# PSU.net
KiCad netlist of a schematic drawn in EAGLE
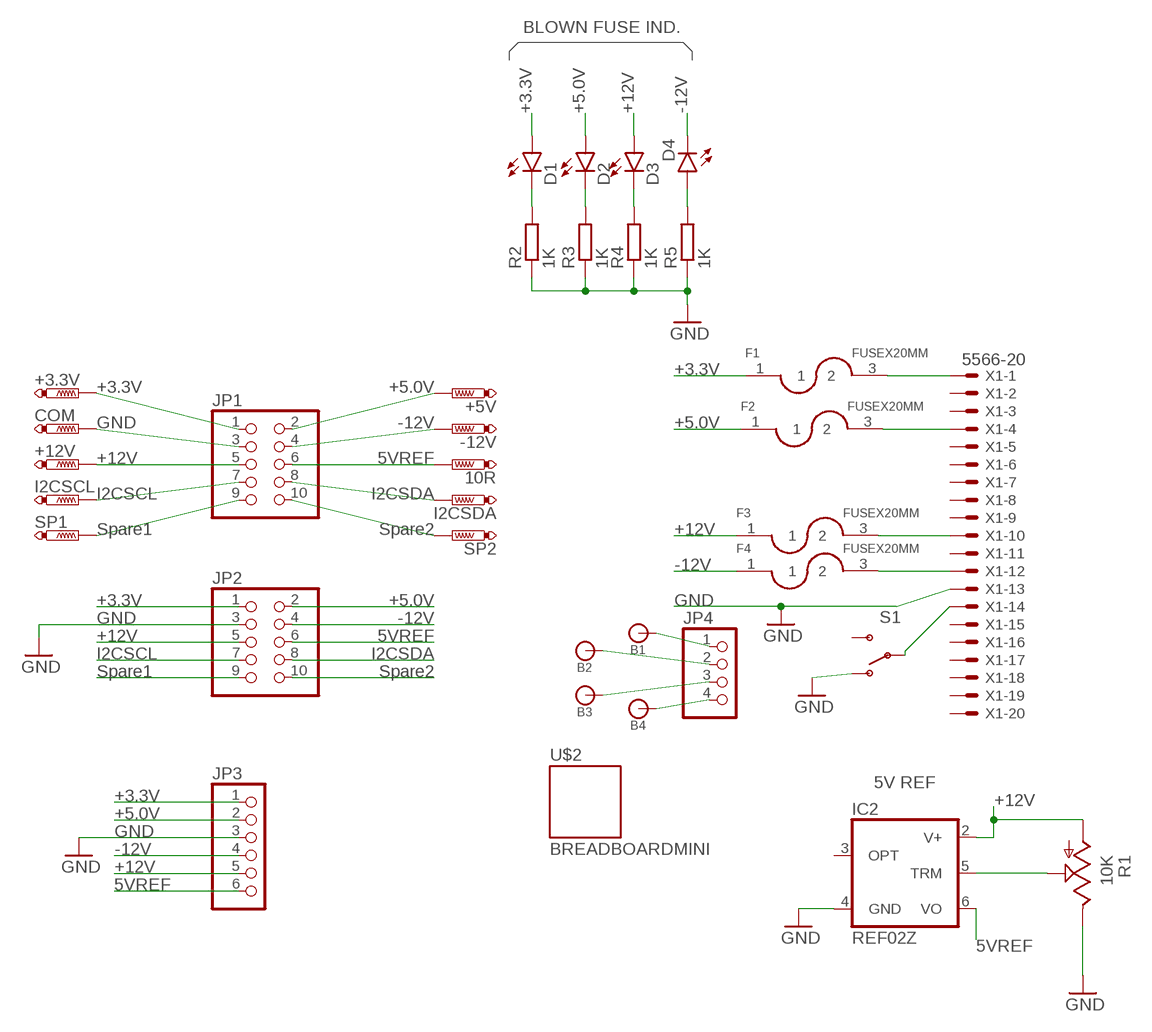
[diagram p0: schematic, sheet 1]

(export (version "E")
  (design (tool "Eeschema 10.0.6"))
  (components
    (comp (ref "+3.3V")
      (value "PTR1B1,27")
      (footprint "eagle-import:B1,27")
      (libsource (lib "eagle-import") (part "PTR1B1,27"))
    )
    (comp (ref "+5V")
      (value "PTR1B1,27")
      (footprint "eagle-import:B1,27")
      (libsource (lib "eagle-import") (part "PTR1B1,27"))
    )
    (comp (ref "+12V")
      (value "PTR1B1,27")
      (footprint "eagle-import:B1,27")
      (libsource (lib "eagle-import") (part "PTR1B1,27"))
    )
    (comp (ref "-12V")
      (value "PTR1B1,27")
      (footprint "eagle-import:B1,27")
      (libsource (lib "eagle-import") (part "PTR1B1,27"))
    )
    (comp (ref "10R")
      (value "PTR1B1,27")
      (footprint "eagle-import:B1,27")
      (libsource (lib "eagle-import") (part "PTR1B1,27"))
    )
    (comp (ref "B1")
      (value "BANANA_CONN")
      (footprint "eagle-import:BANANA_CONN")
      (libsource (lib "eagle-import") (part "BANANA_CONN"))
    )
    (comp (ref "B2")
      (value "BANANA_CONN")
      (footprint "eagle-import:BANANA_CONN")
      (libsource (lib "eagle-import") (part "BANANA_CONN"))
    )
    (comp (ref "B3")
      (value "BANANA_CONN")
      (footprint "eagle-import:BANANA_CONN")
      (libsource (lib "eagle-import") (part "BANANA_CONN"))
    )
    (comp (ref "B4")
      (value "BANANA_CONN")
      (footprint "eagle-import:BANANA_CONN")
      (libsource (lib "eagle-import") (part "BANANA_CONN"))
    )
    (comp (ref "COM")
      (value "PTR1B1,27")
      (footprint "eagle-import:B1,27")
      (libsource (lib "eagle-import") (part "PTR1B1,27"))
    )
    (comp (ref "D1")
      (value "LED5MM")
      (footprint "eagle-import:LED5MM")
      (libsource (lib "eagle-import") (part "LED5MM"))
    )
    (comp (ref "D2")
      (value "LED5MM")
      (footprint "eagle-import:LED5MM")
      (libsource (lib "eagle-import") (part "LED5MM"))
    )
    (comp (ref "D3")
      (value "LED5MM")
      (footprint "eagle-import:LED5MM")
      (libsource (lib "eagle-import") (part "LED5MM"))
    )
    (comp (ref "D4")
      (value "LED5MM")
      (footprint "eagle-import:LED5MM")
      (libsource (lib "eagle-import") (part "LED5MM"))
    )
    (comp (ref "F1")
      (value "FUSEX20MM")
      (footprint "eagle-import:FUSE_5MM")
      (libsource (lib "eagle-import") (part "FUSEX20MM"))
    )
    (comp (ref "F2")
      (value "FUSEX20MM")
      (footprint "eagle-import:FUSE_5MM")
      (libsource (lib "eagle-import") (part "FUSEX20MM"))
    )
    (comp (ref "F3")
      (value "FUSEX20MM")
      (footprint "eagle-import:FUSE_5MM")
      (libsource (lib "eagle-import") (part "FUSEX20MM"))
    )
    (comp (ref "F4")
      (value "FUSEX20MM")
      (footprint "eagle-import:FUSE_5MM")
      (libsource (lib "eagle-import") (part "FUSEX20MM"))
    )
    (comp (ref "I2CSCL")
      (value "PTR1B1,27")
      (footprint "eagle-import:B1,27")
      (libsource (lib "eagle-import") (part "PTR1B1,27"))
    )
    (comp (ref "I2CSDA")
      (value "PTR1B1,27")
      (footprint "eagle-import:B1,27")
      (libsource (lib "eagle-import") (part "PTR1B1,27"))
    )
    (comp (ref "IC2")
      (value "REF02Z")
      (footprint "eagle-import:DIL08")
      (libsource (lib "eagle-import") (part "REF02Z"))
    )
    (comp (ref "JP1")
      (value "PINHD-2X5/90")
      (footprint "eagle-import:2X05_90")
      (libsource (lib "eagle-import") (part "PINHD-2X5/90"))
    )
    (comp (ref "JP2")
      (value "PINHD-2X5/90")
      (footprint "eagle-import:2X05_90")
      (libsource (lib "eagle-import") (part "PINHD-2X5/90"))
    )
    (comp (ref "JP3")
      (value "PINHD-1X6")
      (footprint "eagle-import:1X06")
      (libsource (lib "eagle-import") (part "PINHD-1X6"))
    )
    (comp (ref "JP4")
      (value "PINHD-1X4")
      (footprint "eagle-import:1X04")
      (libsource (lib "eagle-import") (part "PINHD-1X4"))
    )
    (comp (ref "R1")
      (value "10K")
      (footprint "eagle-import:PT-10")
      (libsource (lib "eagle-import") (part "TRIM_US-PT-10"))
    )
    (comp (ref "R2")
      (value "1K")
      (footprint "eagle-import:RTH025W")
      (libsource (lib "eagle-import") (part "RESISTOR-PTH-0.4"))
    )
    (comp (ref "R3")
      (value "1K")
      (footprint "eagle-import:RTH025W")
      (libsource (lib "eagle-import") (part "RESISTOR-PTH-0.4"))
    )
    (comp (ref "R4")
      (value "1K")
      (footprint "eagle-import:RTH025W")
      (libsource (lib "eagle-import") (part "RESISTOR-PTH-0.4"))
    )
    (comp (ref "R5")
      (value "1K")
      (footprint "eagle-import:RTH025W")
      (libsource (lib "eagle-import") (part "RESISTOR-PTH-0.4"))
    )
    (comp (ref "S1")
      (value "SWITCH-SPDTPTH")
      (footprint "eagle-import:SWITCH-SPDT")
      (libsource (lib "eagle-import") (part "SWITCH-SPDTPTH"))
    )
    (comp (ref "SP1")
      (value "PTR1B1,27")
      (footprint "eagle-import:B1,27")
      (libsource (lib "eagle-import") (part "PTR1B1,27"))
    )
    (comp (ref "SP2")
      (value "PTR1B1,27")
      (footprint "eagle-import:B1,27")
      (libsource (lib "eagle-import") (part "PTR1B1,27"))
    )
    (comp (ref "U$2")
      (value "BREADBOARDMINI")
      (footprint "eagle-import:BREADBOARD-MINI")
      (libsource (lib "eagle-import") (part "BREADBOARDMINI"))
    )
    (comp (ref "X1")
      (value "5566-20")
      (footprint "eagle-import:5566-20")
      (libsource (lib "eagle-import") (part "5566-20"))
    )
  )
  (nets
    (net (code "1") (name "/+3.3V") (class "Default")
      (node (ref "+3.3V") (pin "TP") (pinfunction "TP_TP") (pintype "input"))
      (node (ref "D1") (pin "A") (pinfunction "A_A") (pintype "passive"))
      (node (ref "F1") (pin "1") (pinfunction "1_1") (pintype "bidirectional"))
      (node (ref "JP1") (pin "1") (pinfunction "1_1") (pintype "passive"))
      (node (ref "JP2") (pin "1") (pinfunction "1_1") (pintype "passive"))
      (node (ref "JP3") (pin "1") (pinfunction "1_1") (pintype "passive"))
    )
    (net (code "2") (name "/+5.0V") (class "Default")
      (node (ref "+5V") (pin "TP") (pinfunction "TP_TP") (pintype "input"))
      (node (ref "D2") (pin "A") (pinfunction "A_A") (pintype "passive"))
      (node (ref "F2") (pin "1") (pinfunction "1_1") (pintype "bidirectional"))
      (node (ref "JP1") (pin "2") (pinfunction "2_2") (pintype "passive"))
      (node (ref "JP2") (pin "2") (pinfunction "2_2") (pintype "passive"))
      (node (ref "JP3") (pin "2") (pinfunction "2_2") (pintype "passive"))
    )
    (net (code "3") (name "/+12V") (class "Default")
      (node (ref "+12V") (pin "TP") (pinfunction "TP_TP") (pintype "input"))
      (node (ref "D3") (pin "A") (pinfunction "A_A") (pintype "passive"))
      (node (ref "F3") (pin "1") (pinfunction "1_1") (pintype "bidirectional"))
      (node (ref "IC2") (pin "2") (pinfunction "V+_2") (pintype "power_in"))
      (node (ref "JP1") (pin "5") (pinfunction "5_5") (pintype "passive"))
      (node (ref "JP2") (pin "5") (pinfunction "5_5") (pintype "passive"))
      (node (ref "JP3") (pin "5") (pinfunction "5_5") (pintype "passive"))
      (node (ref "R1") (pin "A") (pinfunction "A_A") (pintype "passive"))
    )
    (net (code "4") (name "/-12V") (class "Default")
      (node (ref "-12V") (pin "TP") (pinfunction "TP_TP") (pintype "input"))
      (node (ref "D4") (pin "K") (pinfunction "C_K") (pintype "passive"))
      (node (ref "F4") (pin "1") (pinfunction "1_1") (pintype "bidirectional"))
      (node (ref "JP1") (pin "4") (pinfunction "4_4") (pintype "passive"))
      (node (ref "JP2") (pin "4") (pinfunction "4_4") (pintype "passive"))
      (node (ref "JP3") (pin "4") (pinfunction "4_4") (pintype "passive"))
    )
    (net (code "5") (name "/5VREF") (class "Default")
      (node (ref "10R") (pin "TP") (pinfunction "TP_TP") (pintype "input"))
      (node (ref "IC2") (pin "6") (pinfunction "VO_6") (pintype "output"))
      (node (ref "JP1") (pin "6") (pinfunction "6_6") (pintype "passive"))
      (node (ref "JP2") (pin "6") (pinfunction "6_6") (pintype "passive"))
      (node (ref "JP3") (pin "6") (pinfunction "6_6") (pintype "passive"))
    )
    (net (code "6") (name "/I2CSCL") (class "Default")
      (node (ref "I2CSCL") (pin "TP") (pinfunction "TP_TP") (pintype "input"))
      (node (ref "JP1") (pin "7") (pinfunction "7_7") (pintype "passive"))
      (node (ref "JP2") (pin "7") (pinfunction "7_7") (pintype "passive"))
    )
    (net (code "7") (name "/I2CSDA") (class "Default")
      (node (ref "I2CSDA") (pin "TP") (pinfunction "TP_TP") (pintype "input"))
      (node (ref "JP1") (pin "8") (pinfunction "8_8") (pintype "passive"))
      (node (ref "JP2") (pin "8") (pinfunction "8_8") (pintype "passive"))
    )
    (net (code "8") (name "/SPARE1") (class "Default")
      (node (ref "JP1") (pin "9") (pinfunction "9_9") (pintype "passive"))
      (node (ref "JP2") (pin "9") (pinfunction "9_9") (pintype "passive"))
      (node (ref "SP1") (pin "TP") (pinfunction "TP_TP") (pintype "input"))
    )
    (net (code "9") (name "/SPARE2") (class "Default")
      (node (ref "JP1") (pin "10") (pinfunction "10_10") (pintype "passive"))
      (node (ref "JP2") (pin "10") (pinfunction "10_10") (pintype "passive"))
      (node (ref "SP2") (pin "TP") (pinfunction "TP_TP") (pintype "input"))
    )
    (net (code "10") (name "GND") (class "Default")
      (node (ref "COM") (pin "TP") (pinfunction "TP_TP") (pintype "input"))
      (node (ref "IC2") (pin "4") (pinfunction "GND_4") (pintype "power_in"))
      (node (ref "JP1") (pin "3") (pinfunction "3_3") (pintype "passive"))
      (node (ref "JP2") (pin "3") (pinfunction "3_3") (pintype "passive"))
      (node (ref "JP3") (pin "3") (pinfunction "3_3") (pintype "passive"))
      (node (ref "R1") (pin "E") (pinfunction "E_E") (pintype "passive"))
      (node (ref "R2") (pin "1") (pinfunction "1_1") (pintype "passive"))
      (node (ref "R3") (pin "1") (pinfunction "1_1") (pintype "passive"))
      (node (ref "R4") (pin "1") (pinfunction "1_1") (pintype "passive"))
      (node (ref "R5") (pin "1") (pinfunction "1_1") (pintype "passive"))
      (node (ref "S1") (pin "1") (pinfunction "O_1") (pintype "passive"))
      (node (ref "X1") (pin "13") (pinfunction "S_13") (pintype "passive"))
    )
    (net (code "11") (name "Net-(B1-1)") (class "Default")
      (node (ref "B1") (pin "P$1") (pinfunction "1_P$1") (pintype "passive"))
      (node (ref "JP4") (pin "1") (pinfunction "1_1") (pintype "passive"))
    )
    (net (code "12") (name "Net-(B2-1)") (class "Default")
      (node (ref "B2") (pin "P$1") (pinfunction "1_P$1") (pintype "passive"))
      (node (ref "JP4") (pin "2") (pinfunction "2_2") (pintype "passive"))
    )
    (net (code "13") (name "Net-(B3-1)") (class "Default")
      (node (ref "B3") (pin "P$1") (pinfunction "1_P$1") (pintype "passive"))
      (node (ref "JP4") (pin "3") (pinfunction "3_3") (pintype "passive"))
    )
    (net (code "14") (name "Net-(B4-1)") (class "Default")
      (node (ref "B4") (pin "P$1") (pinfunction "1_P$1") (pintype "passive"))
      (node (ref "JP4") (pin "4") (pinfunction "4_4") (pintype "passive"))
    )
    (net (code "15") (name "Net-(D1-C)") (class "Default")
      (node (ref "D1") (pin "K") (pinfunction "C_K") (pintype "passive"))
      (node (ref "R2") (pin "2") (pinfunction "2_2") (pintype "passive"))
    )
    (net (code "16") (name "Net-(D2-C)") (class "Default")
      (node (ref "D2") (pin "K") (pinfunction "C_K") (pintype "passive"))
      (node (ref "R3") (pin "2") (pinfunction "2_2") (pintype "passive"))
    )
    (net (code "17") (name "Net-(D3-C)") (class "Default")
      (node (ref "D3") (pin "K") (pinfunction "C_K") (pintype "passive"))
      (node (ref "R4") (pin "2") (pinfunction "2_2") (pintype "passive"))
    )
    (net (code "18") (name "Net-(D4-PadA)") (class "Default")
      (node (ref "D4") (pin "A") (pinfunction "A_A") (pintype "passive"))
      (node (ref "R5") (pin "2") (pinfunction "2_2") (pintype "passive"))
    )
    (net (code "19") (name "Net-(F1-2)") (class "Default")
      (node (ref "F1") (pin "3") (pinfunction "2_3") (pintype "bidirectional"))
      (node (ref "X1") (pin "1") (pinfunction "S_1") (pintype "passive"))
    )
    (net (code "20") (name "Net-(F2-2)") (class "Default")
      (node (ref "F2") (pin "3") (pinfunction "2_3") (pintype "bidirectional"))
      (node (ref "X1") (pin "4") (pinfunction "S_4") (pintype "passive"))
    )
    (net (code "21") (name "Net-(F3-2)") (class "Default")
      (node (ref "F3") (pin "3") (pinfunction "2_3") (pintype "bidirectional"))
      (node (ref "X1") (pin "10") (pinfunction "S_10") (pintype "passive"))
    )
    (net (code "22") (name "Net-(F4-2)") (class "Default")
      (node (ref "F4") (pin "3") (pinfunction "2_3") (pintype "bidirectional"))
      (node (ref "X1") (pin "12") (pinfunction "S_12") (pintype "passive"))
    )
    (net (code "23") (name "Net-(IC2-TRM)") (class "Default")
      (node (ref "IC2") (pin "5") (pinfunction "TRM_5") (pintype "input"))
      (node (ref "R1") (pin "S") (pinfunction "S_S") (pintype "passive"))
    )
    (net (code "24") (name "Net-(S1-P)") (class "Default")
      (node (ref "S1") (pin "2") (pinfunction "P_2") (pintype "passive"))
      (node (ref "X1") (pin "14") (pinfunction "S_14") (pintype "passive"))
    )
    (net (code "25") (name "unconnected-(IC2-OPT-Pad3)") (class "Default")
      (node (ref "IC2") (pin "3") (pinfunction "OPT_3") (pintype "output"))
    )
    (net (code "26") (name "unconnected-(S1-S-Pad3)") (class "Default")
      (node (ref "S1") (pin "3") (pinfunction "S_3") (pintype "passive"))
    )
    (net (code "27") (name "unconnected-(X1C-S-Pad11)") (class "Default")
      (node (ref "X1") (pin "11") (pinfunction "S_11") (pintype "passive"))
    )
    (net (code "28") (name "unconnected-(X1G-S-Pad15)") (class "Default")
      (node (ref "X1") (pin "15") (pinfunction "S_15") (pintype "passive"))
    )
    (net (code "29") (name "unconnected-(X1H-S-Pad16)") (class "Default")
      (node (ref "X1") (pin "16") (pinfunction "S_16") (pintype "passive"))
    )
    (net (code "30") (name "unconnected-(X1I-S-Pad17)") (class "Default")
      (node (ref "X1") (pin "17") (pinfunction "S_17") (pintype "passive"))
    )
    (net (code "31") (name "unconnected-(X1J-S-Pad18)") (class "Default")
      (node (ref "X1") (pin "18") (pinfunction "S_18") (pintype "passive"))
    )
    (net (code "32") (name "unconnected-(X1K-S-Pad19)") (class "Default")
      (node (ref "X1") (pin "19") (pinfunction "S_19") (pintype "passive"))
    )
    (net (code "33") (name "unconnected-(X1L-S-Pad2)") (class "Default")
      (node (ref "X1") (pin "2") (pinfunction "S_2") (pintype "passive"))
    )
    (net (code "34") (name "unconnected-(X1M-S-Pad20)") (class "Default")
      (node (ref "X1") (pin "20") (pinfunction "S_20") (pintype "passive"))
    )
    (net (code "35") (name "unconnected-(X1N-S-Pad3)") (class "Default")
      (node (ref "X1") (pin "3") (pinfunction "S_3") (pintype "passive"))
    )
    (net (code "36") (name "unconnected-(X1P-S-Pad5)") (class "Default")
      (node (ref "X1") (pin "5") (pinfunction "S_5") (pintype "passive"))
    )
    (net (code "37") (name "unconnected-(X1Q-S-Pad6)") (class "Default")
      (node (ref "X1") (pin "6") (pinfunction "S_6") (pintype "passive"))
    )
    (net (code "38") (name "unconnected-(X1R-S-Pad7)") (class "Default")
      (node (ref "X1") (pin "7") (pinfunction "S_7") (pintype "passive"))
    )
    (net (code "39") (name "unconnected-(X1S-S-Pad8)") (class "Default")
      (node (ref "X1") (pin "8") (pinfunction "S_8") (pintype "passive"))
    )
    (net (code "40") (name "unconnected-(X1T-S-Pad9)") (class "Default")
      (node (ref "X1") (pin "9") (pinfunction "S_9") (pintype "passive"))
    )
  )
)
